# Big_Coil_Bridge_PCBA.net
KiCad netlist of a schematic drawn in Altium Designer
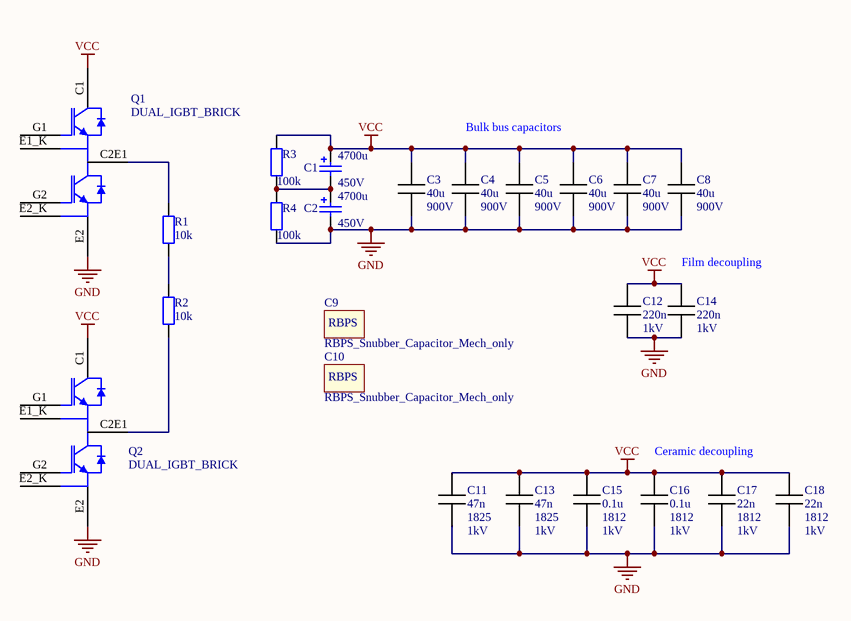
[diagram p0: Big Coil Bridge PCBA.SchDoc]

(export (version "E")
  (design (tool "Eeschema 10.0.6"))
  (components
    (comp (ref "C1")
      (value "4700u")
      (footprint "PEH200YV447BMB2")
      (description "Electrolytic capacitor")
      (fields (field (name "VOLTAGE") "450V") (field (name "Comment") "885012209028"))
      (libsource (lib "TV_Altium_library") (part "Capacitor_Elec"))
    )
    (comp (ref "C2")
      (value "4700u")
      (footprint "PEH200YV447BMB2")
      (description "Electrolytic capacitor")
      (fields (field (name "VOLTAGE") "450V") (field (name "Comment") "885012209028"))
      (libsource (lib "TV_Altium_library") (part "Capacitor_Elec"))
    )
    (comp (ref "C3")
      (value "~")
      (footprint "C4AEOBW5400A3NJ")
      (fields (field (name "CAPACITANCE") "40u") (field (name "VOLTAGE") "900V"))
      (libsource (lib "TV_Altium_library") (part "Capacitor"))
    )
    (comp (ref "C4")
      (value "~")
      (footprint "C4AEOBW5400A3NJ")
      (fields (field (name "CAPACITANCE") "40u") (field (name "VOLTAGE") "900V"))
      (libsource (lib "TV_Altium_library") (part "Capacitor"))
    )
    (comp (ref "C5")
      (value "~")
      (footprint "C4AEOBW5400A3NJ")
      (fields (field (name "CAPACITANCE") "40u") (field (name "VOLTAGE") "900V"))
      (libsource (lib "TV_Altium_library") (part "Capacitor"))
    )
    (comp (ref "C6")
      (value "~")
      (footprint "C4AEOBW5400A3NJ")
      (fields (field (name "CAPACITANCE") "40u") (field (name "VOLTAGE") "900V"))
      (libsource (lib "TV_Altium_library") (part "Capacitor"))
    )
    (comp (ref "C7")
      (value "~")
      (footprint "C4AEOBW5400A3NJ")
      (fields (field (name "CAPACITANCE") "40u") (field (name "VOLTAGE") "900V"))
      (libsource (lib "TV_Altium_library") (part "Capacitor"))
    )
    (comp (ref "C8")
      (value "~")
      (footprint "C4AEOBW5400A3NJ")
      (fields (field (name "CAPACITANCE") "40u") (field (name "VOLTAGE") "900V"))
      (libsource (lib "TV_Altium_library") (part "Capacitor"))
    )
    (comp (ref "C9")
      (value "RBPS_Snubber_Capacitor_Mech_only")
      (footprint "RBPS_R4_OUTLINE")
      (libsource (lib "TV_Altium_library") (part "RBPS_Snubber_Capacitor_Mech_only"))
    )
    (comp (ref "C10")
      (value "RBPS_Snubber_Capacitor_Mech_only")
      (footprint "RBPS_R4_OUTLINE")
      (libsource (lib "TV_Altium_library") (part "RBPS_Snubber_Capacitor_Mech_only"))
    )
    (comp (ref "C11")
      (value "Capacitor")
      (footprint "1825C")
      (fields
        (field (name "CAPACITANCE") "47n")
        (field (name "PACKAGE") "1825")
        (field (name "VOLTAGE") "1kV")
      )
      (libsource (lib "TV_Altium_library") (part "Capacitor"))
    )
    (comp (ref "C12")
      (value "Capacitor")
      (footprint "B32653A0224")
      (fields (field (name "CAPACITANCE") "220n") (field (name "VOLTAGE") "1kV"))
      (libsource (lib "TV_Altium_library") (part "Capacitor"))
    )
    (comp (ref "C13")
      (value "Capacitor")
      (footprint "1825C")
      (fields
        (field (name "CAPACITANCE") "47n")
        (field (name "PACKAGE") "1825")
        (field (name "VOLTAGE") "1kV")
      )
      (libsource (lib "TV_Altium_library") (part "Capacitor"))
    )
    (comp (ref "C14")
      (value "Capacitor")
      (footprint "B32653A0224")
      (fields (field (name "CAPACITANCE") "220n") (field (name "VOLTAGE") "1kV"))
      (libsource (lib "TV_Altium_library") (part "Capacitor"))
    )
    (comp (ref "C15")
      (value "Capacitor")
      (footprint "1812C")
      (fields
        (field (name "CAPACITANCE") "0.1u")
        (field (name "PACKAGE") "1812")
        (field (name "VOLTAGE") "1kV")
      )
      (libsource (lib "TV_Altium_library") (part "Capacitor"))
    )
    (comp (ref "C16")
      (value "Capacitor")
      (footprint "1812C")
      (fields
        (field (name "CAPACITANCE") "0.1u")
        (field (name "PACKAGE") "1812")
        (field (name "VOLTAGE") "1kV")
      )
      (libsource (lib "TV_Altium_library") (part "Capacitor"))
    )
    (comp (ref "C17")
      (value "Capacitor")
      (footprint "1812C")
      (fields
        (field (name "CAPACITANCE") "22n")
        (field (name "PACKAGE") "1812")
        (field (name "VOLTAGE") "1kV")
      )
      (libsource (lib "TV_Altium_library") (part "Capacitor"))
    )
    (comp (ref "C18")
      (value "Capacitor")
      (footprint "1812C")
      (fields
        (field (name "CAPACITANCE") "22n")
        (field (name "PACKAGE") "1812")
        (field (name "VOLTAGE") "1kV")
      )
      (libsource (lib "TV_Altium_library") (part "Capacitor"))
    )
    (comp (ref "Q1")
      (value "DUAL_IGBT_BRICK")
      (footprint "CM300/SKM200_DUAL_FOOTPRINT_2")
      (description "IGBT, DUAL, BRICK")
      (libsource (lib "TV_Altium_library") (part "DUAL_IGBT_BRICK"))
    )
    (comp (ref "Q2")
      (value "DUAL_IGBT_BRICK")
      (footprint "CM300/SKM200_DUAL_FOOTPRINT_2")
      (description "IGBT, DUAL, BRICK")
      (libsource (lib "TV_Altium_library") (part "DUAL_IGBT_BRICK"))
    )
    (comp (ref "R1")
      (value "Resistor")
      (footprint "Res_Axial_0.6in")
      (fields (field (name "PARAMETER 1") "10k"))
      (libsource (lib "TV_Altium_library") (part "Resistor"))
    )
    (comp (ref "R2")
      (value "Resistor")
      (footprint "Res_Axial_0.6in")
      (fields (field (name "PARAMETER 1") "10k"))
      (libsource (lib "TV_Altium_library") (part "Resistor"))
    )
    (comp (ref "R3")
      (value "Resistor")
      (footprint "Res_Axial_0.6in")
      (fields (field (name "PARAMETER 1") "100k"))
      (libsource (lib "TV_Altium_library") (part "Resistor"))
    )
    (comp (ref "R4")
      (value "Resistor")
      (footprint "Res_Axial_0.6in")
      (fields (field (name "PARAMETER 1") "100k"))
      (libsource (lib "TV_Altium_library") (part "Resistor"))
    )
  )
  (nets
    (net (code "1") (name "GND") (class "Default")
      (node (ref "C11") (pin "2") (pinfunction "2_2") (pintype "passive"))
      (node (ref "C12") (pin "2") (pinfunction "2_2") (pintype "passive"))
      (node (ref "C13") (pin "2") (pinfunction "2_2") (pintype "passive"))
      (node (ref "C14") (pin "2") (pinfunction "2_2") (pintype "passive"))
      (node (ref "C15") (pin "2") (pinfunction "2_2") (pintype "passive"))
      (node (ref "C16") (pin "2") (pinfunction "2_2") (pintype "passive"))
      (node (ref "C17") (pin "2") (pinfunction "2_2") (pintype "passive"))
      (node (ref "C18") (pin "2") (pinfunction "2_2") (pintype "passive"))
      (node (ref "C2") (pin "2") (pinfunction "N_2") (pintype "passive"))
      (node (ref "C3") (pin "2") (pinfunction "2_2") (pintype "passive"))
      (node (ref "C4") (pin "2") (pinfunction "2_2") (pintype "passive"))
      (node (ref "C5") (pin "2") (pinfunction "2_2") (pintype "passive"))
      (node (ref "C6") (pin "2") (pinfunction "2_2") (pintype "passive"))
      (node (ref "C7") (pin "2") (pinfunction "2_2") (pintype "passive"))
      (node (ref "C8") (pin "2") (pinfunction "2_2") (pintype "passive"))
      (node (ref "Q1") (pin "E2") (pinfunction "E_E2") (pintype "passive"))
      (node (ref "Q2") (pin "E2") (pinfunction "E_E2") (pintype "passive"))
      (node (ref "R4") (pin "1") (pinfunction "1_1") (pintype "passive"))
    )
    (net (code "2") (name "Net-(C1-N)") (class "Default")
      (node (ref "C1") (pin "2") (pinfunction "N_2") (pintype "passive"))
      (node (ref "C2") (pin "1") (pinfunction "P_1") (pintype "passive"))
      (node (ref "R3") (pin "1") (pinfunction "1_1") (pintype "passive"))
      (node (ref "R4") (pin "2") (pinfunction "2_2") (pintype "passive"))
    )
    (net (code "3") (name "Net-(Q1-PadC2E1)") (class "Default")
      (node (ref "Q1") (pin "C2E1") (pintype "passive"))
      (node (ref "R1") (pin "2") (pinfunction "2_2") (pintype "passive"))
    )
    (net (code "4") (name "Net-(Q2-PadC2E1)") (class "Default")
      (node (ref "Q2") (pin "C2E1") (pintype "passive"))
      (node (ref "R2") (pin "1") (pinfunction "1_1") (pintype "passive"))
    )
    (net (code "5") (name "Net-(R1-Pad1)") (class "Default")
      (node (ref "R1") (pin "1") (pinfunction "1_1") (pintype "passive"))
      (node (ref "R2") (pin "2") (pinfunction "2_2") (pintype "passive"))
    )
    (net (code "6") (name "VCC") (class "Default")
      (node (ref "C1") (pin "1") (pinfunction "P_1") (pintype "passive"))
      (node (ref "C11") (pin "1") (pinfunction "1_1") (pintype "passive"))
      (node (ref "C12") (pin "1") (pinfunction "1_1") (pintype "passive"))
      (node (ref "C13") (pin "1") (pinfunction "1_1") (pintype "passive"))
      (node (ref "C14") (pin "1") (pinfunction "1_1") (pintype "passive"))
      (node (ref "C15") (pin "1") (pinfunction "1_1") (pintype "passive"))
      (node (ref "C16") (pin "1") (pinfunction "1_1") (pintype "passive"))
      (node (ref "C17") (pin "1") (pinfunction "1_1") (pintype "passive"))
      (node (ref "C18") (pin "1") (pinfunction "1_1") (pintype "passive"))
      (node (ref "C3") (pin "1") (pinfunction "1_1") (pintype "passive"))
      (node (ref "C4") (pin "1") (pinfunction "1_1") (pintype "passive"))
      (node (ref "C5") (pin "1") (pinfunction "1_1") (pintype "passive"))
      (node (ref "C6") (pin "1") (pinfunction "1_1") (pintype "passive"))
      (node (ref "C7") (pin "1") (pinfunction "1_1") (pintype "passive"))
      (node (ref "C8") (pin "1") (pinfunction "1_1") (pintype "passive"))
      (node (ref "Q1") (pin "C1") (pinfunction "C_C1") (pintype "passive"))
      (node (ref "Q2") (pin "C1") (pinfunction "C_C1") (pintype "passive"))
      (node (ref "R3") (pin "2") (pinfunction "2_2") (pintype "passive"))
    )
    (net (code "7") (name "unconnected-(Q1-E-PadE1_K)") (class "Default")
      (node (ref "Q1") (pin "E1_K") (pinfunction "E_E1_K") (pintype "passive"))
    )
    (net (code "8") (name "unconnected-(Q1-G-PadG1)") (class "Default")
      (node (ref "Q1") (pin "G1") (pinfunction "G_G1") (pintype "passive"))
    )
    (net (code "9") (name "unconnected-(Q1-G-PadG2)") (class "Default")
      (node (ref "Q1") (pin "G2") (pinfunction "G_G2") (pintype "passive"))
    )
    (net (code "10") (name "unconnected-(Q1-PadE2_K)") (class "Default")
      (node (ref "Q1") (pin "E2_K") (pintype "passive"))
    )
    (net (code "11") (name "unconnected-(Q2-E-PadE1_K)") (class "Default")
      (node (ref "Q2") (pin "E1_K") (pinfunction "E_E1_K") (pintype "passive"))
    )
    (net (code "12") (name "unconnected-(Q2-G-PadG1)") (class "Default")
      (node (ref "Q2") (pin "G1") (pinfunction "G_G1") (pintype "passive"))
    )
    (net (code "13") (name "unconnected-(Q2-G-PadG2)") (class "Default")
      (node (ref "Q2") (pin "G2") (pinfunction "G_G2") (pintype "passive"))
    )
    (net (code "14") (name "unconnected-(Q2-PadE2_K)") (class "Default")
      (node (ref "Q2") (pin "E2_K") (pintype "passive"))
    )
  )
)
